# VCSEL.net
KiCad netlist of a schematic drawn in Altium Designer
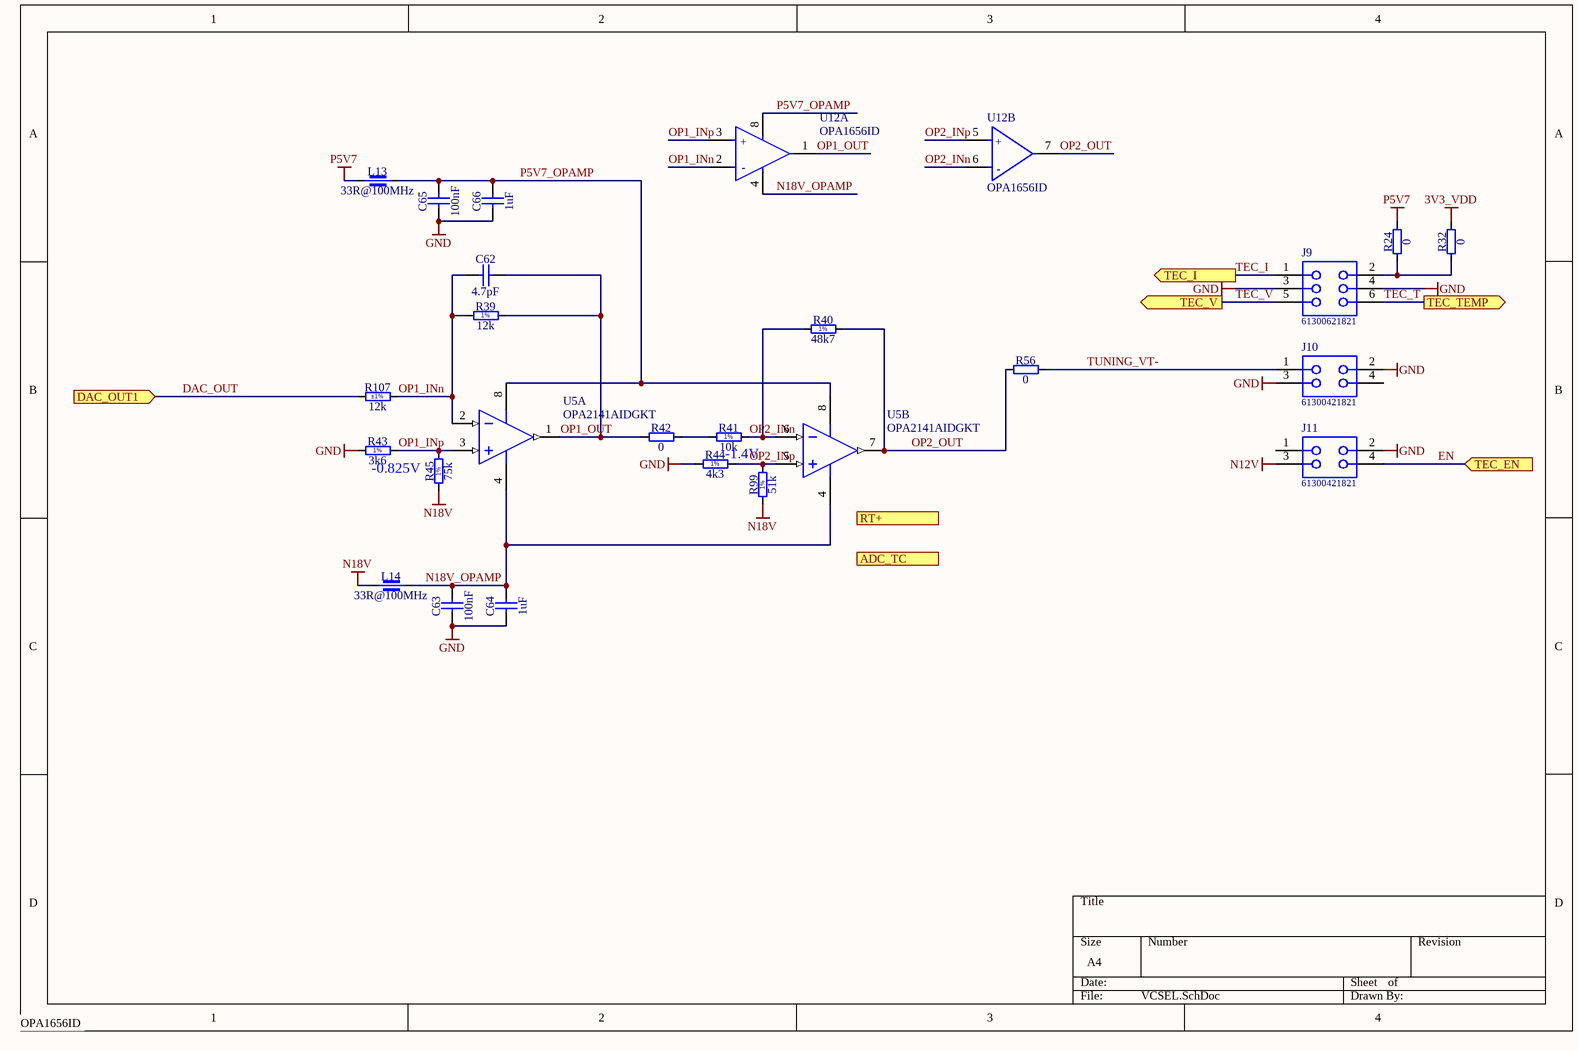
[diagram p0: VCSEL.SchDoc]

(export (version "E")
  (design (tool "Eeschema 10.0.6"))
  (components
    (comp (ref "C62")
      (value "4.7pF")
      (footprint "CAPC1005X55N")
      (description "Non-polarised capacitor")
      (fields
        (field (name "PART NUMBER") "CC0402_4.7PF_50V_0.25PF_C0G")
        (field (name "VOLTAGE") "50V")
        (field (name "AUTHOR") "CERN DEM JLC")
      )
      (libsource (lib "Capacitors") (part "Capacitor - non polarized"))
    )
    (comp (ref "C63")
      (value "100nF")
      (footprint "CAPC1608X87N")
      (description "Non-polarised capacitor")
      (fields
        (field (name "PART NUMBER") "CC0603_100NF_50V_10%_X5R")
        (field (name "VOLTAGE") "50V")
        (field (name "AUTHOR") "CERN DEM MR")
      )
      (libsource (lib "Capacitors") (part "Capacitor - non polarized"))
    )
    (comp (ref "C64")
      (value "1uF")
      (footprint "CAPC1608X87N")
      (description "Non-polarised capacitor")
      (fields
        (field (name "PART NUMBER") "CC0603_1UF_25V_10%_X7R")
        (field (name "VOLTAGE") "25V")
        (field (name "AUTHOR") "CERN DEM JLC")
      )
      (libsource (lib "Capacitors") (part "Capacitor - non polarized"))
    )
    (comp (ref "C65")
      (value "100nF")
      (footprint "CAPC1005X55N")
      (description "Non-polarised capacitor")
      (fields
        (field (name "PART NUMBER") "CC0402_100NF_16V_10%_X7R")
        (field (name "VOLTAGE") "16V")
        (field (name "AUTHOR") "CERN DEM JLC")
      )
      (libsource (lib "Capacitors") (part "Capacitor - non polarized"))
    )
    (comp (ref "C66")
      (value "1uF")
      (footprint "CAPC1005X55N")
      (description "Non-polarised capacitor")
      (fields
        (field (name "PART NUMBER") "CC0402_1UF_16V_10%_X5R")
        (field (name "VOLTAGE") "16V")
        (field (name "AUTHOR") "CERN DEM JLC")
      )
      (libsource (lib "Capacitors") (part "Capacitor - non polarized"))
    )
    (comp (ref "J9")
      (value "61300621821")
      (footprint "61300621821")
      (description "WR-PHD Socket Header, THT, pitch 2.54mm, Dual Row, Vertical, 6p")
      (fields (field (name "MANUFACTURER") "Wurth Elektronik"))
      (libsource (lib "Altium_WR-PHD (rev20a)") (part "61300621821"))
    )
    (comp (ref "J10")
      (value "61300421821")
      (footprint "61300421821")
      (description "WR-PHD Socket Header, THT, pitch 2.54mm, Dual Row, Vertical, 4p")
      (fields (field (name "MANUFACTURER") "Wurth Elektronik"))
      (libsource (lib "Altium_WR-PHD (rev20a)") (part "61300421821"))
    )
    (comp (ref "J11")
      (value "61300421821")
      (footprint "61300421821")
      (description "WR-PHD Socket Header, THT, pitch 2.54mm, Dual Row, Vertical, 4p")
      (fields (field (name "MANUFACTURER") "Wurth Elektronik"))
      (libsource (lib "Altium_WR-PHD (rev20a)") (part "61300421821"))
    )
    (comp (ref "L13")
      (value "33R@100MHz")
      (footprint "INDC1005X55N")
      (fields
        (field (name "PART NUMBER") "IND0402_MURATA_BLM15PX330SN1D")
        (field (name "POWER") "3A")
        (field (name "TOLERANCE") "±25%")
        (field (name "AUTHOR") "CERN DEM JMW")
      )
      (libsource (lib "Inductors & Transformers") (part "Ferrite Bead"))
    )
    (comp (ref "L14")
      (value "33R@100MHz")
      (footprint "INDC1005X55N")
      (fields
        (field (name "PART NUMBER") "IND0402_MURATA_BLM15PX330SN1D")
        (field (name "POWER") "3A")
        (field (name "TOLERANCE") "±25%")
        (field (name "AUTHOR") "CERN DEM JMW")
      )
      (libsource (lib "Inductors & Transformers") (part "Ferrite Bead"))
    )
    (comp (ref "R24")
      (value "0")
      (footprint "RESC2012X60N")
      (description "Resistor")
      (fields
        (field (name "PART NUMBER") "R0805_0R_JUMPER")
        (field (name "MANUFACTURER") "GENERIC")
        (field (name "AUTHOR") "CERN DEM JLC")
      )
      (libsource (lib "Resistors") (part "Resistor"))
    )
    (comp (ref "R32")
      (value "0")
      (footprint "RESC2012X60N")
      (description "Resistor")
      (fields
        (field (name "PART NUMBER") "R0805_0R_JUMPER")
        (field (name "MANUFACTURER") "GENERIC")
        (field (name "AUTHOR") "CERN DEM JLC")
      )
      (libsource (lib "Resistors") (part "Resistor"))
    )
    (comp (ref "R39")
      (value "12k")
      (footprint "RESC1005X40N")
      (description "Resistor - 1%")
      (fields
        (field (name "PART NUMBER") "R0402_12K_1%_0.0625W_100PPM")
        (field (name "POWER") "0.0625W")
        (field (name "AUTHOR") "CERN DEM JLC")
      )
      (libsource (lib "Resistors") (part "Resistor - 1%"))
    )
    (comp (ref "R40")
      (value "48k7")
      (footprint "RESC1608X55N")
      (description "Resistor - 1%")
      (fields
        (field (name "PART NUMBER") "R0603_48K7_1%_0.1W_100PPM")
        (field (name "POWER") "0.1W")
        (field (name "AUTHOR") "CERN DEM JLC")
      )
      (libsource (lib "Resistors") (part "Resistor - 1%"))
    )
    (comp (ref "R41")
      (value "10k")
      (footprint "RESC1005X40N")
      (description "Resistor - 1%")
      (fields
        (field (name "PART NUMBER") "R0402_10K_1%_0.0625W_100PPM")
        (field (name "POWER") "0.0625W")
        (field (name "AUTHOR") "CERN DEM JLC")
      )
      (libsource (lib "Resistors") (part "Resistor - 1%"))
    )
    (comp (ref "R42")
      (value "0")
      (footprint "RESC1005X40N")
      (description "Resistor")
      (fields
        (field (name "PART NUMBER") "R0402_0R_JUMPER")
        (field (name "MANUFACTURER") "GENERIC")
        (field (name "AUTHOR") "CERN DEM JLC")
      )
      (libsource (lib "Resistors") (part "Resistor"))
    )
    (comp (ref "R43")
      (value "3k6")
      (footprint "RESC1005X40N")
      (description "Resistor - 1%")
      (fields
        (field (name "PART NUMBER") "R0402_3K6_1%_0.0625W_100PPM")
        (field (name "POWER") "0.0625W")
        (field (name "AUTHOR") "CERN DEM JLC")
      )
      (libsource (lib "Resistors") (part "Resistor - 1%"))
    )
    (comp (ref "R44")
      (value "4k3")
      (footprint "RESC1005X40N")
      (description "Resistor - 1%")
      (fields
        (field (name "PART NUMBER") "R0402_4K3_1%_0.0625W_100PPM")
        (field (name "POWER") "0.0625W")
        (field (name "AUTHOR") "CERN DEM JLC")
      )
      (libsource (lib "Resistors") (part "Resistor - 1%"))
    )
    (comp (ref "R45")
      (value "75k")
      (footprint "RESC1005X40N")
      (description "Resistor - 1%")
      (fields
        (field (name "PART NUMBER") "R0402_75K_1%_0.0625W_100PPM")
        (field (name "POWER") "0.0625W")
        (field (name "AUTHOR") "CERN DEM JLC")
      )
      (libsource (lib "Resistors") (part "Resistor - 1%"))
    )
    (comp (ref "R56")
      (value "0")
      (footprint "RESC1005X40N")
      (description "Resistor")
      (fields
        (field (name "PART NUMBER") "R0402_0R_JUMPER")
        (field (name "MANUFACTURER") "GENERIC")
        (field (name "AUTHOR") "CERN DEM JLC")
      )
      (libsource (lib "Resistors") (part "Resistor"))
    )
    (comp (ref "R99")
      (value "51k")
      (footprint "RESC1005X40N")
      (description "Resistor - 1%")
      (fields
        (field (name "PART NUMBER") "R0402_51K_1%_0.0625W_100PPM")
        (field (name "POWER") "0.0625W")
        (field (name "AUTHOR") "CERN DEM JLC")
      )
      (libsource (lib "Resistors") (part "Resistor - 1%"))
    )
    (comp (ref "R107")
      (value "12k")
      (footprint "RESC1005X40N")
      (description "Resistor - 1%")
      (fields
        (field (name "PART NUMBER") "R0402_12K_1%_0.0625W_100PPM")
        (field (name "MANUFACTURER") "GENERIC")
        (field (name "TOLERANCE") "±1%")
        (field (name "AUTHOR") "CERN DEM JLC")
      )
      (libsource (lib "Resistors") (part "Resistor - 1%"))
    )
    (comp (ref "U5")
      (value "OPA2141AIDGKT")
      (footprint "DGK0008A_M")
      (fields (field (name "MANUFACTURER") "Texas Instruments"))
      (libsource (lib "Altium Content Vault") (part "TI-OPA-8_2"))
    )
    (comp (ref "U12")
      (value "OPA1656ID")
      (footprint "FP-D0008A-MFG")
      (description "IC AUDIO 2 CIRCUIT 8SOIC")
      (libsource (lib "Altium Content Vault") (part "499df5fc91ff7ad023bcaf249d8becd"))
    )
  )
  (nets
    (net (code "2") (name "/DAC_OUT") (class "Default")
      (node (ref "R107") (pin "1") (pinfunction "1_1") (pintype "passive"))
    )
    (net (code "3") (name "/EN") (class "Default")
      (node (ref "J11") (pin "4") (pinfunction "4_4") (pintype "passive"))
    )
    (net (code "4") (name "/N18V_OPAMP") (class "Default")
      (node (ref "C63") (pin "2") (pinfunction "2_2") (pintype "passive"))
      (node (ref "C64") (pin "2") (pinfunction "2_2") (pintype "passive"))
      (node (ref "L14") (pin "2") (pinfunction "2_2") (pintype "passive"))
      (node (ref "U12") (pin "4") (pinfunction "V-_4") (pintype "power_in"))
      (node (ref "U5") (pin "4") (pinfunction "V-_4") (pintype "power_in"))
    )
    (net (code "5") (name "/OP1_INn") (class "Default")
      (node (ref "C62") (pin "1") (pinfunction "1_1") (pintype "passive"))
      (node (ref "R107") (pin "2") (pinfunction "2_2") (pintype "passive"))
      (node (ref "R39") (pin "1") (pinfunction "1_1") (pintype "passive"))
      (node (ref "U12") (pin "2") (pinfunction "-IN_A_2") (pintype "tri_state"))
      (node (ref "U5") (pin "2") (pinfunction "IN_A-_2") (pintype "input"))
    )
    (net (code "6") (name "/OP1_INp") (class "Default")
      (node (ref "R43") (pin "2") (pinfunction "2_2") (pintype "passive"))
      (node (ref "R45") (pin "2") (pinfunction "2_2") (pintype "passive"))
      (node (ref "U12") (pin "3") (pinfunction "+IN_A_3") (pintype "tri_state"))
      (node (ref "U5") (pin "3") (pinfunction "IN_A+_3") (pintype "input"))
    )
    (net (code "7") (name "/OP1_OUT") (class "Default")
      (node (ref "C62") (pin "2") (pinfunction "2_2") (pintype "passive"))
      (node (ref "R39") (pin "2") (pinfunction "2_2") (pintype "passive"))
      (node (ref "R42") (pin "1") (pinfunction "1_1") (pintype "passive"))
      (node (ref "U12") (pin "1") (pinfunction "OUT_A_1") (pintype "passive"))
      (node (ref "U5") (pin "1") (pinfunction "OUT_A_1") (pintype "output"))
    )
    (net (code "8") (name "/OP2_INn") (class "Default")
      (node (ref "R40") (pin "1") (pinfunction "1_1") (pintype "passive"))
      (node (ref "R41") (pin "2") (pinfunction "2_2") (pintype "passive"))
      (node (ref "U12") (pin "6") (pinfunction "-IN_B_6") (pintype "tri_state"))
      (node (ref "U5") (pin "6") (pinfunction "IN_B-_6") (pintype "input"))
    )
    (net (code "9") (name "/OP2_INp") (class "Default")
      (node (ref "R44") (pin "2") (pinfunction "2_2") (pintype "passive"))
      (node (ref "R99") (pin "2") (pinfunction "2_2") (pintype "passive"))
      (node (ref "U12") (pin "5") (pinfunction "+IN_B_5") (pintype "tri_state"))
      (node (ref "U5") (pin "5") (pinfunction "IN_B+_5") (pintype "input"))
    )
    (net (code "10") (name "/OP2_OUT") (class "Default")
      (node (ref "R40") (pin "2") (pinfunction "2_2") (pintype "passive"))
      (node (ref "R56") (pin "1") (pinfunction "1_1") (pintype "passive"))
      (node (ref "U12") (pin "7") (pinfunction "OUT_B_7") (pintype "passive"))
      (node (ref "U5") (pin "7") (pinfunction "OUT_B_7") (pintype "output"))
    )
    (net (code "11") (name "/P5V7_OPAMP") (class "Default")
      (node (ref "C65") (pin "2") (pinfunction "2_2") (pintype "passive"))
      (node (ref "C66") (pin "2") (pinfunction "2_2") (pintype "passive"))
      (node (ref "L13") (pin "2") (pinfunction "2_2") (pintype "passive"))
      (node (ref "U12") (pin "8") (pinfunction "V+_8") (pintype "power_in"))
      (node (ref "U5") (pin "8") (pinfunction "V+_8") (pintype "power_in"))
    )
    (net (code "13") (name "/TEC_I") (class "Default")
      (node (ref "J9") (pin "1") (pinfunction "1_1") (pintype "passive"))
    )
    (net (code "14") (name "/TEC_T") (class "Default")
      (node (ref "J9") (pin "6") (pinfunction "6_6") (pintype "passive"))
    )
    (net (code "15") (name "/TEC_V") (class "Default")
      (node (ref "J9") (pin "5") (pinfunction "5_5") (pintype "passive"))
    )
    (net (code "16") (name "/TUNING_VT-") (class "Default")
      (node (ref "J10") (pin "1") (pinfunction "1_1") (pintype "passive"))
      (node (ref "R56") (pin "2") (pinfunction "2_2") (pintype "passive"))
    )
    (net (code "17") (name "3V3_VDD") (class "Default")
      (node (ref "R32") (pin "2") (pinfunction "2_2") (pintype "passive"))
    )
    (net (code "18") (name "GND") (class "Default")
      (node (ref "C63") (pin "1") (pinfunction "1_1") (pintype "passive"))
      (node (ref "C64") (pin "1") (pinfunction "1_1") (pintype "passive"))
      (node (ref "C65") (pin "1") (pinfunction "1_1") (pintype "passive"))
      (node (ref "C66") (pin "1") (pinfunction "1_1") (pintype "passive"))
      (node (ref "J10") (pin "2") (pinfunction "2_2") (pintype "passive"))
      (node (ref "J10") (pin "3") (pinfunction "3_3") (pintype "passive"))
      (node (ref "J11") (pin "2") (pinfunction "2_2") (pintype "passive"))
      (node (ref "J9") (pin "3") (pinfunction "3_3") (pintype "passive"))
      (node (ref "J9") (pin "4") (pinfunction "4_4") (pintype "passive"))
      (node (ref "R43") (pin "1") (pinfunction "1_1") (pintype "passive"))
      (node (ref "R44") (pin "1") (pinfunction "1_1") (pintype "passive"))
    )
    (net (code "19") (name "N12V") (class "Default")
      (node (ref "J11") (pin "3") (pinfunction "3_3") (pintype "passive"))
    )
    (net (code "20") (name "N18V") (class "Default")
      (node (ref "L14") (pin "1") (pinfunction "1_1") (pintype "passive"))
      (node (ref "R45") (pin "1") (pinfunction "1_1") (pintype "passive"))
      (node (ref "R99") (pin "1") (pinfunction "1_1") (pintype "passive"))
    )
    (net (code "21") (name "Net-(J9-Pad2)") (class "Default")
      (node (ref "J9") (pin "2") (pinfunction "2_2") (pintype "passive"))
      (node (ref "R24") (pin "1") (pinfunction "1_1") (pintype "passive"))
      (node (ref "R32") (pin "1") (pinfunction "1_1") (pintype "passive"))
    )
    (net (code "22") (name "Net-(R41-Pad1)") (class "Default")
      (node (ref "R41") (pin "1") (pinfunction "1_1") (pintype "passive"))
      (node (ref "R42") (pin "2") (pinfunction "2_2") (pintype "passive"))
    )
    (net (code "23") (name "P5V7") (class "Default")
      (node (ref "L13") (pin "1") (pinfunction "1_1") (pintype "passive"))
      (node (ref "R24") (pin "2") (pinfunction "2_2") (pintype "passive"))
    )
    (net (code "24") (name "unconnected-(J10-Pad4)") (class "Default")
      (node (ref "J10") (pin "4") (pinfunction "4_4") (pintype "passive"))
    )
    (net (code "25") (name "unconnected-(J11-Pad1)") (class "Default")
      (node (ref "J11") (pin "1") (pinfunction "1_1") (pintype "passive"))
    )
  )
)
